# SCH_plantcare_moisture_module_2025-02-17.net
KiCad netlist of a schematic drawn in EasyEDA
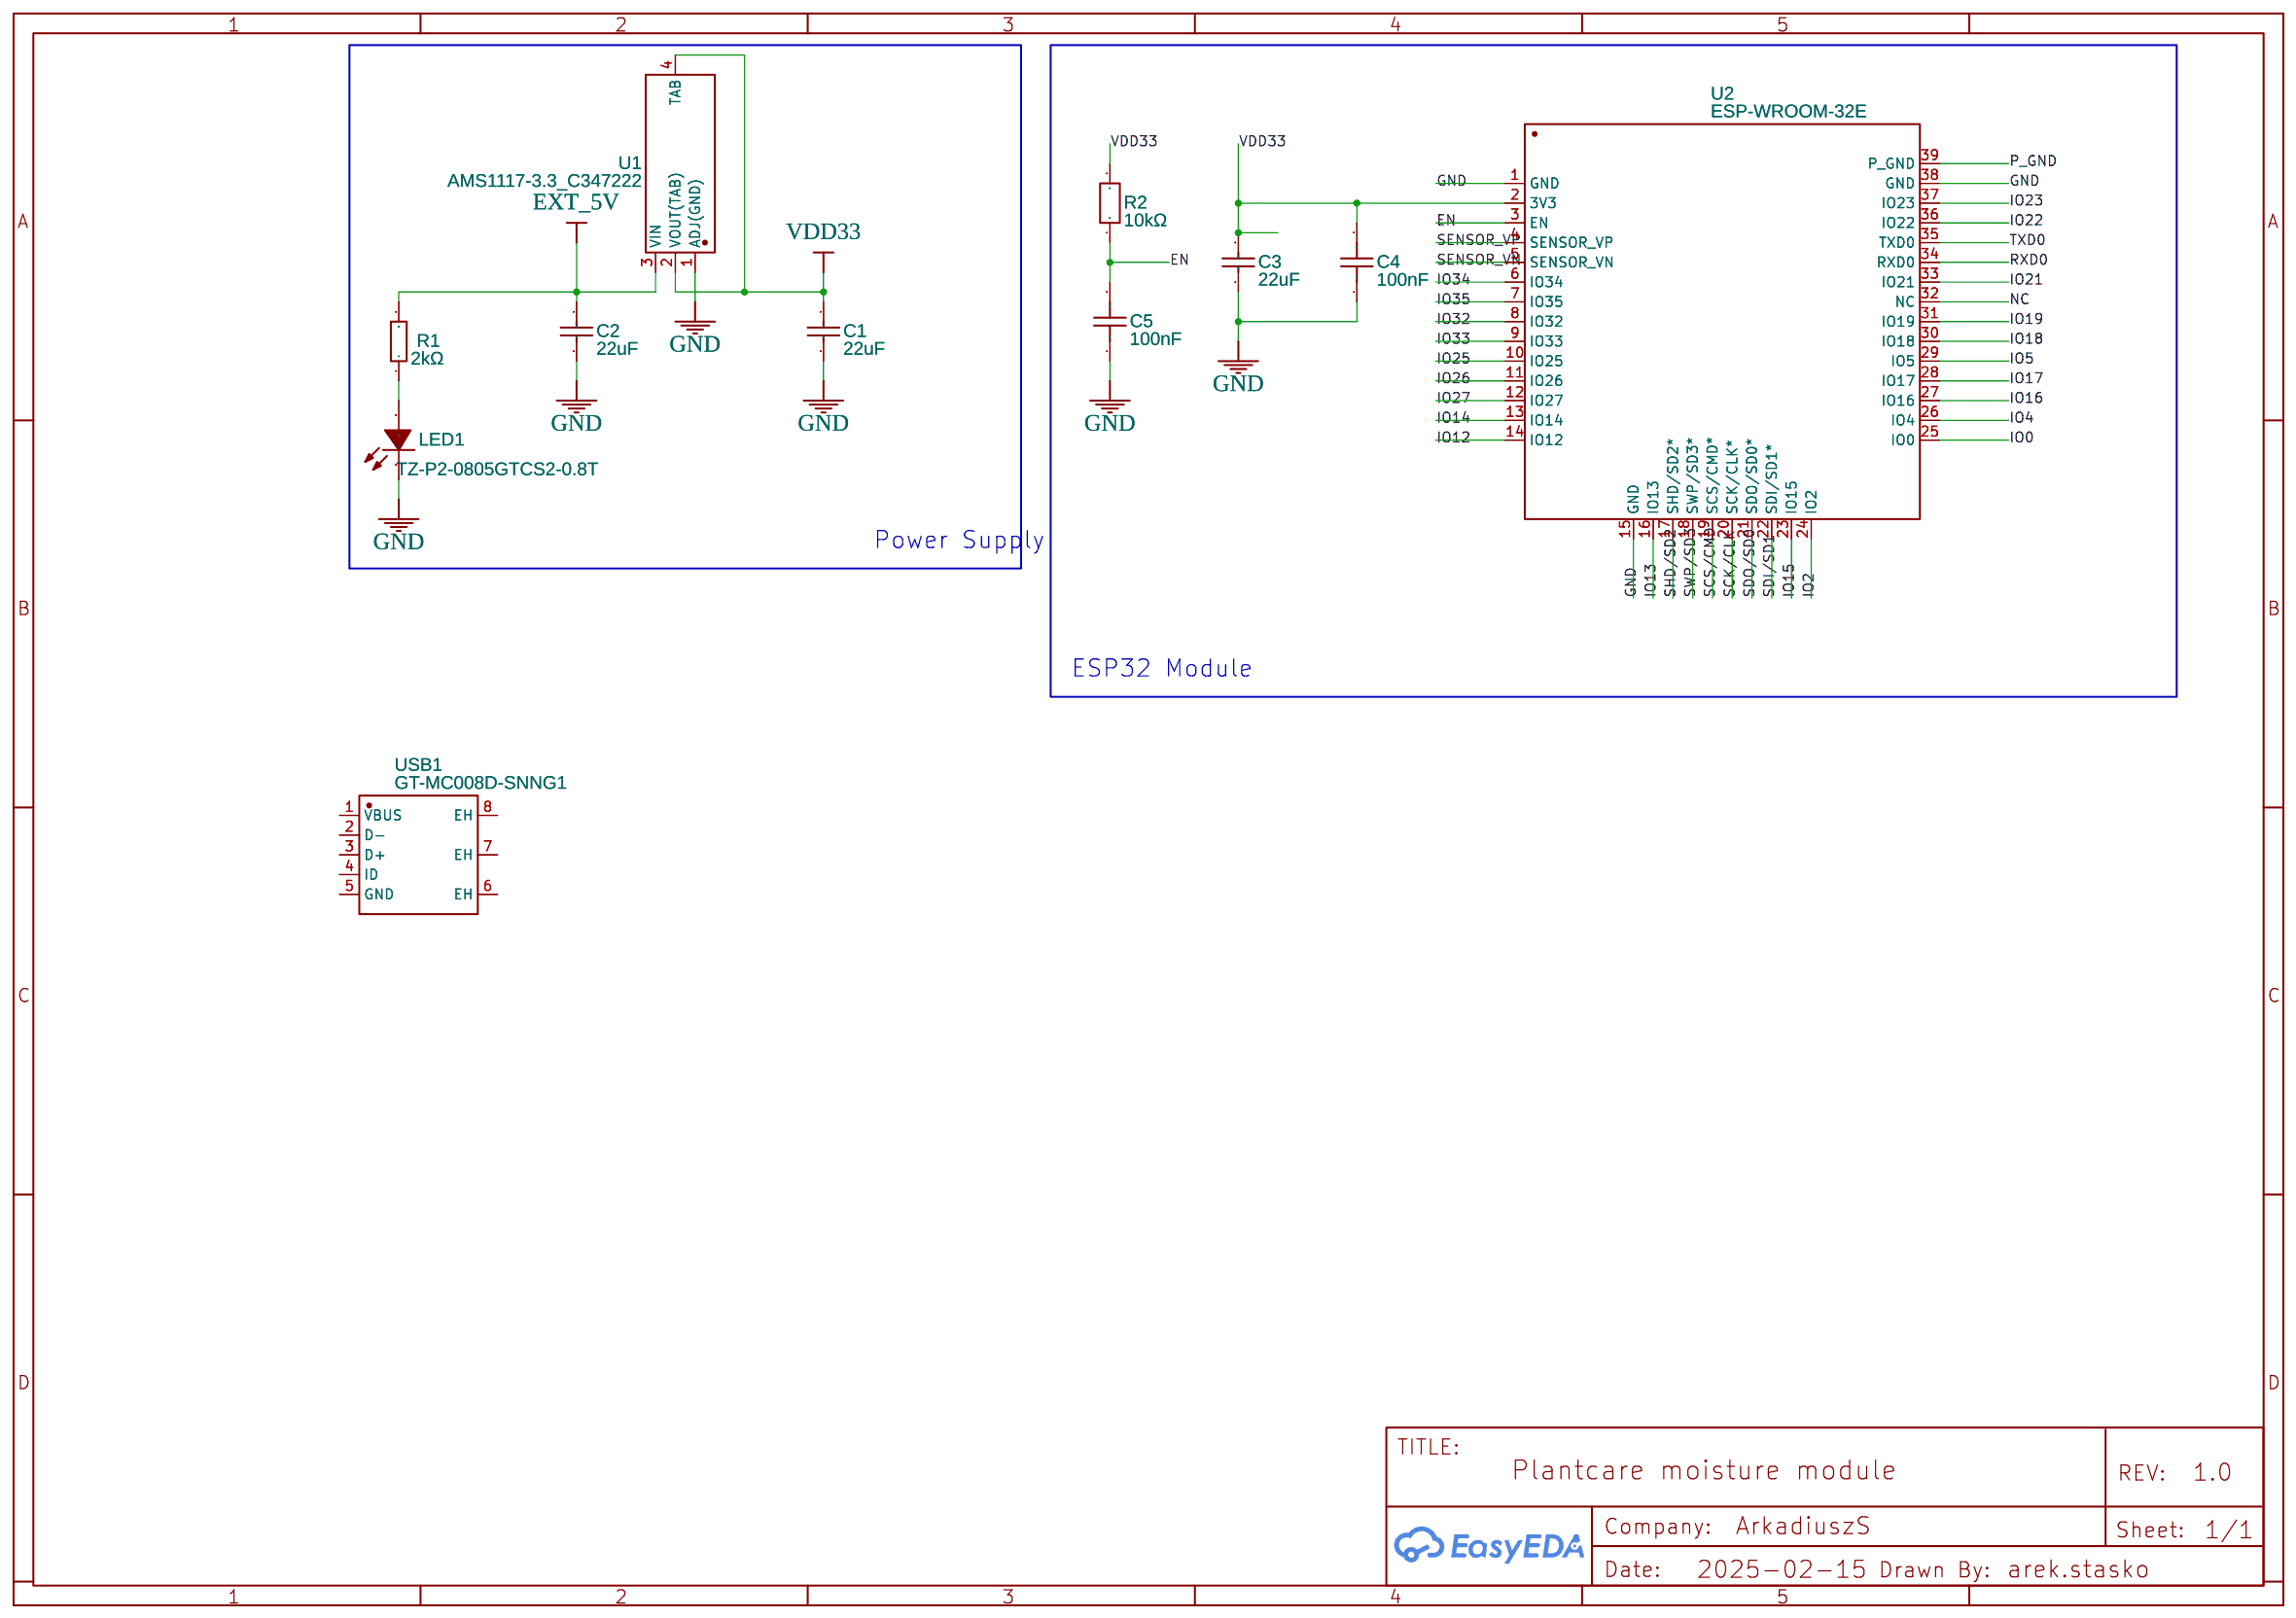
[diagram p0: schematic sheet]

(export (version "E")
  (design (tool "Eeschema 10.0.6"))
  (components
    (comp (ref "C1")
      (value "22uF")
      (fields
        (field (name "Manufacturer Part") "CL21A226MPQNNNE")
        (field (name "Manufacturer") "SAMSUNG(三星)")
      )
      (libsource (lib "") (part "CL21A226MPQNNNE"))
    )
    (comp (ref "C2")
      (value "22uF")
      (fields
        (field (name "Manufacturer Part") "CL21A226MPQNNNE")
        (field (name "Manufacturer") "SAMSUNG(三星)")
      )
      (libsource (lib "") (part "CL21A226MPQNNNE"))
    )
    (comp (ref "C3")
      (value "22uF")
      (fields
        (field (name "Manufacturer Part") "CL21A226MPQNNNE")
        (field (name "Manufacturer") "SAMSUNG(三星)")
      )
      (libsource (lib "") (part "CL21A226MPQNNNE"))
    )
    (comp (ref "C4")
      (value "100nF")
      (fields
        (field (name "Manufacturer Part") "CL10B104KB8NNNC")
        (field (name "Manufacturer") "SAMSUNG(三星)")
      )
      (libsource (lib "") (part "CL10B104KB8NNNC"))
    )
    (comp (ref "C5")
      (value "100nF")
      (fields
        (field (name "Manufacturer Part") "CL10B104KB8NNNC")
        (field (name "Manufacturer") "SAMSUNG(三星)")
      )
      (libsource (lib "") (part "CL10B104KB8NNNC"))
    )
    (comp (ref "LED1")
      (value "TZ-P2-0805GTCS2-0.8T")
      (fields (field (name "Manufacturer") "TUOZHAN(拓展光电)"))
      (libsource (lib "") (part "TZ-P2-0805GTCS2-0.8T"))
    )
    (comp (ref "R1")
      (value "2kΩ")
      (fields
        (field (name "Manufacturer Part") "0603WAF2001T5E")
        (field (name "Manufacturer") "UNI-ROYAL(厚声)")
      )
      (libsource (lib "") (part "0603WAF2001T5E"))
    )
    (comp (ref "R2")
      (value "10kΩ")
      (fields (field (name "Manufacturer Part") "FRC0603J103TS") (field (name "Manufacturer") "FOJAN(富捷)"))
      (libsource (lib "") (part "FRC0603J103TS"))
    )
    (comp (ref "U1")
      (value "AMS1117-3.3_C347222")
      (fields (field (name "Manufacturer Part") "AMS1117-3.3") (field (name "Manufacturer") "UMW(友台半导体)"))
      (libsource (lib "") (part "AMS1117-3.3_C347222"))
    )
    (comp (ref "U2")
      (value "ESP-WROOM-32E")
      (fields (field (name "Manufacturer") "DOIT(四博智联)"))
      (libsource (lib "") (part "ESP-WROOM-32E"))
    )
    (comp (ref "USB1")
      (value "GT-MC008D-SNNG1")
      (fields (field (name "Manufacturer") "G-Switch(品赞)"))
      (libsource (lib "") (part "GT-MC008D-SNNG1"))
    )
  )
  (nets
    (net (code "1") (name "/EN") (class "Default")
      (node (ref "C5") (pin "2") (pinfunction "2_2") (pintype "unspecified"))
      (node (ref "R2") (pin "1") (pinfunction "1_1") (pintype "unspecified"))
      (node (ref "U2") (pin "3") (pinfunction "EN_3") (pintype "unspecified"))
    )
    (net (code "2") (name "/IO0") (class "Default")
      (node (ref "U2") (pin "25") (pinfunction "IO0_25") (pintype "unspecified"))
    )
    (net (code "3") (name "/IO2") (class "Default")
      (node (ref "U2") (pin "24") (pinfunction "IO2_24") (pintype "unspecified"))
    )
    (net (code "4") (name "/IO4") (class "Default")
      (node (ref "U2") (pin "26") (pinfunction "IO4_26") (pintype "unspecified"))
    )
    (net (code "5") (name "/IO5") (class "Default")
      (node (ref "U2") (pin "29") (pinfunction "IO5_29") (pintype "unspecified"))
    )
    (net (code "6") (name "/IO12") (class "Default")
      (node (ref "U2") (pin "14") (pinfunction "IO12_14") (pintype "unspecified"))
    )
    (net (code "7") (name "/IO13") (class "Default")
      (node (ref "U2") (pin "16") (pinfunction "IO13_16") (pintype "unspecified"))
    )
    (net (code "8") (name "/IO14") (class "Default")
      (node (ref "U2") (pin "13") (pinfunction "IO14_13") (pintype "unspecified"))
    )
    (net (code "9") (name "/IO15") (class "Default")
      (node (ref "U2") (pin "23") (pinfunction "IO15_23") (pintype "unspecified"))
    )
    (net (code "10") (name "/IO16") (class "Default")
      (node (ref "U2") (pin "27") (pinfunction "IO16_27") (pintype "unspecified"))
    )
    (net (code "11") (name "/IO17") (class "Default")
      (node (ref "U2") (pin "28") (pinfunction "IO17_28") (pintype "unspecified"))
    )
    (net (code "12") (name "/IO18") (class "Default")
      (node (ref "U2") (pin "30") (pinfunction "IO18_30") (pintype "unspecified"))
    )
    (net (code "13") (name "/IO19") (class "Default")
      (node (ref "U2") (pin "31") (pinfunction "IO19_31") (pintype "unspecified"))
    )
    (net (code "14") (name "/IO21") (class "Default")
      (node (ref "U2") (pin "33") (pinfunction "IO21_33") (pintype "unspecified"))
    )
    (net (code "15") (name "/IO22") (class "Default")
      (node (ref "U2") (pin "36") (pinfunction "IO22_36") (pintype "unspecified"))
    )
    (net (code "16") (name "/IO23") (class "Default")
      (node (ref "U2") (pin "37") (pinfunction "IO23_37") (pintype "unspecified"))
    )
    (net (code "17") (name "/IO25") (class "Default")
      (node (ref "U2") (pin "10") (pinfunction "IO25_10") (pintype "unspecified"))
    )
    (net (code "18") (name "/IO26") (class "Default")
      (node (ref "U2") (pin "11") (pinfunction "IO26_11") (pintype "unspecified"))
    )
    (net (code "19") (name "/IO27") (class "Default")
      (node (ref "U2") (pin "12") (pinfunction "IO27_12") (pintype "unspecified"))
    )
    (net (code "20") (name "/IO32") (class "Default")
      (node (ref "U2") (pin "8") (pinfunction "IO32_8") (pintype "unspecified"))
    )
    (net (code "21") (name "/IO33") (class "Default")
      (node (ref "U2") (pin "9") (pinfunction "IO33_9") (pintype "unspecified"))
    )
    (net (code "22") (name "/IO34") (class "Default")
      (node (ref "U2") (pin "6") (pinfunction "IO34_6") (pintype "unspecified"))
    )
    (net (code "23") (name "/IO35") (class "Default")
      (node (ref "U2") (pin "7") (pinfunction "IO35_7") (pintype "unspecified"))
    )
    (net (code "24") (name "/NC") (class "Default")
      (node (ref "U2") (pin "32") (pinfunction "NC_32") (pintype "unspecified"))
    )
    (net (code "25") (name "/P_GND") (class "Default")
      (node (ref "U2") (pin "39") (pinfunction "P_GND_39") (pintype "unspecified"))
    )
    (net (code "26") (name "/RXD0") (class "Default")
      (node (ref "U2") (pin "34") (pinfunction "RXD0_34") (pintype "unspecified"))
    )
    (net (code "27") (name "/SCK{slash}CLK") (class "Default")
      (node (ref "U2") (pin "20") (pinfunction "SCK/CLK*_20") (pintype "unspecified"))
    )
    (net (code "28") (name "/SCS{slash}CMD") (class "Default")
      (node (ref "U2") (pin "19") (pinfunction "SCS/CMD*_19") (pintype "unspecified"))
    )
    (net (code "29") (name "/SDI{slash}SD1") (class "Default")
      (node (ref "U2") (pin "22") (pinfunction "SDI/SD1*_22") (pintype "unspecified"))
    )
    (net (code "30") (name "/SDO{slash}SD0") (class "Default")
      (node (ref "U2") (pin "21") (pinfunction "SDO/SD0*_21") (pintype "unspecified"))
    )
    (net (code "31") (name "/SENSOR_VN") (class "Default")
      (node (ref "U2") (pin "5") (pinfunction "SENSOR_VN_5") (pintype "unspecified"))
    )
    (net (code "32") (name "/SENSOR_VP") (class "Default")
      (node (ref "U2") (pin "4") (pinfunction "SENSOR_VP_4") (pintype "unspecified"))
    )
    (net (code "33") (name "/SHD{slash}SD2") (class "Default")
      (node (ref "U2") (pin "17") (pinfunction "SHD/SD2*_17") (pintype "unspecified"))
    )
    (net (code "34") (name "/SWP{slash}SD3") (class "Default")
      (node (ref "U2") (pin "18") (pinfunction "SWP/SD3*_18") (pintype "unspecified"))
    )
    (net (code "35") (name "/TXD0") (class "Default")
      (node (ref "U2") (pin "35") (pinfunction "TXD0_35") (pintype "unspecified"))
    )
    (net (code "36") (name "EXT_5V") (class "Default")
      (node (ref "C2") (pin "2") (pinfunction "2_2") (pintype "input"))
      (node (ref "R1") (pin "2") (pinfunction "2_2") (pintype "input"))
      (node (ref "U1") (pin "3") (pinfunction "VIN_3") (pintype "unspecified"))
    )
    (net (code "37") (name "GND") (class "Default")
      (node (ref "C1") (pin "1") (pinfunction "1_1") (pintype "input"))
      (node (ref "C2") (pin "1") (pinfunction "1_1") (pintype "input"))
      (node (ref "C3") (pin "1") (pinfunction "1_1") (pintype "input"))
      (node (ref "C4") (pin "1") (pinfunction "1_1") (pintype "unspecified"))
      (node (ref "C5") (pin "1") (pinfunction "1_1") (pintype "unspecified"))
      (node (ref "LED1") (pin "1") (pinfunction "-_1") (pintype "unspecified"))
      (node (ref "U1") (pin "1") (pinfunction "ADJ(GND)_1") (pintype "unspecified"))
      (node (ref "U2") (pin "1") (pinfunction "GND_1") (pintype "unspecified"))
      (node (ref "U2") (pin "15") (pinfunction "GND_15") (pintype "unspecified"))
      (node (ref "U2") (pin "38") (pinfunction "GND_38") (pintype "unspecified"))
    )
    (net (code "38") (name "Net-(LED1-+)") (class "Default")
      (node (ref "LED1") (pin "2") (pinfunction "+_2") (pintype "unspecified"))
      (node (ref "R1") (pin "1") (pinfunction "1_1") (pintype "input"))
    )
    (net (code "39") (name "VDD33") (class "Default")
      (node (ref "C1") (pin "2") (pinfunction "2_2") (pintype "input"))
      (node (ref "C3") (pin "2") (pinfunction "2_2") (pintype "input"))
      (node (ref "C4") (pin "2") (pinfunction "2_2") (pintype "unspecified"))
      (node (ref "R2") (pin "2") (pinfunction "2_2") (pintype "unspecified"))
      (node (ref "U1") (pin "2") (pinfunction "VOUT(TAB)_2") (pintype "unspecified"))
      (node (ref "U1") (pin "4") (pinfunction "TAB_4") (pintype "unspecified"))
      (node (ref "U2") (pin "2") (pinfunction "3V3_2") (pintype "unspecified"))
    )
    (net (code "40") (name "unconnected-(USB1-D+-Pad3)") (class "Default")
      (node (ref "USB1") (pin "3") (pinfunction "D+_3") (pintype "unspecified"))
    )
    (net (code "41") (name "unconnected-(USB1-D--Pad2)") (class "Default")
      (node (ref "USB1") (pin "2") (pinfunction "D-_2") (pintype "unspecified"))
    )
    (net (code "42") (name "unconnected-(USB1-EH-Pad6)") (class "Default")
      (node (ref "USB1") (pin "6") (pinfunction "EH_6") (pintype "unspecified"))
    )
    (net (code "43") (name "unconnected-(USB1-EH-Pad7)") (class "Default")
      (node (ref "USB1") (pin "7") (pinfunction "EH_7") (pintype "unspecified"))
    )
    (net (code "44") (name "unconnected-(USB1-EH-Pad8)") (class "Default")
      (node (ref "USB1") (pin "8") (pinfunction "EH_8") (pintype "unspecified"))
    )
    (net (code "45") (name "unconnected-(USB1-GND-Pad5)") (class "Default")
      (node (ref "USB1") (pin "5") (pinfunction "GND_5") (pintype "unspecified"))
    )
    (net (code "46") (name "unconnected-(USB1-ID-Pad4)") (class "Default")
      (node (ref "USB1") (pin "4") (pinfunction "ID_4") (pintype "unspecified"))
    )
    (net (code "47") (name "unconnected-(USB1-VBUS-Pad1)") (class "Default")
      (node (ref "USB1") (pin "1") (pinfunction "VBUS_1") (pintype "unspecified"))
    )
  )
)
